# SL1_Xilinx_Spartan-IIE_PQ208_Rev1_02.net
KiCad netlist of a schematic drawn in Altium Designer
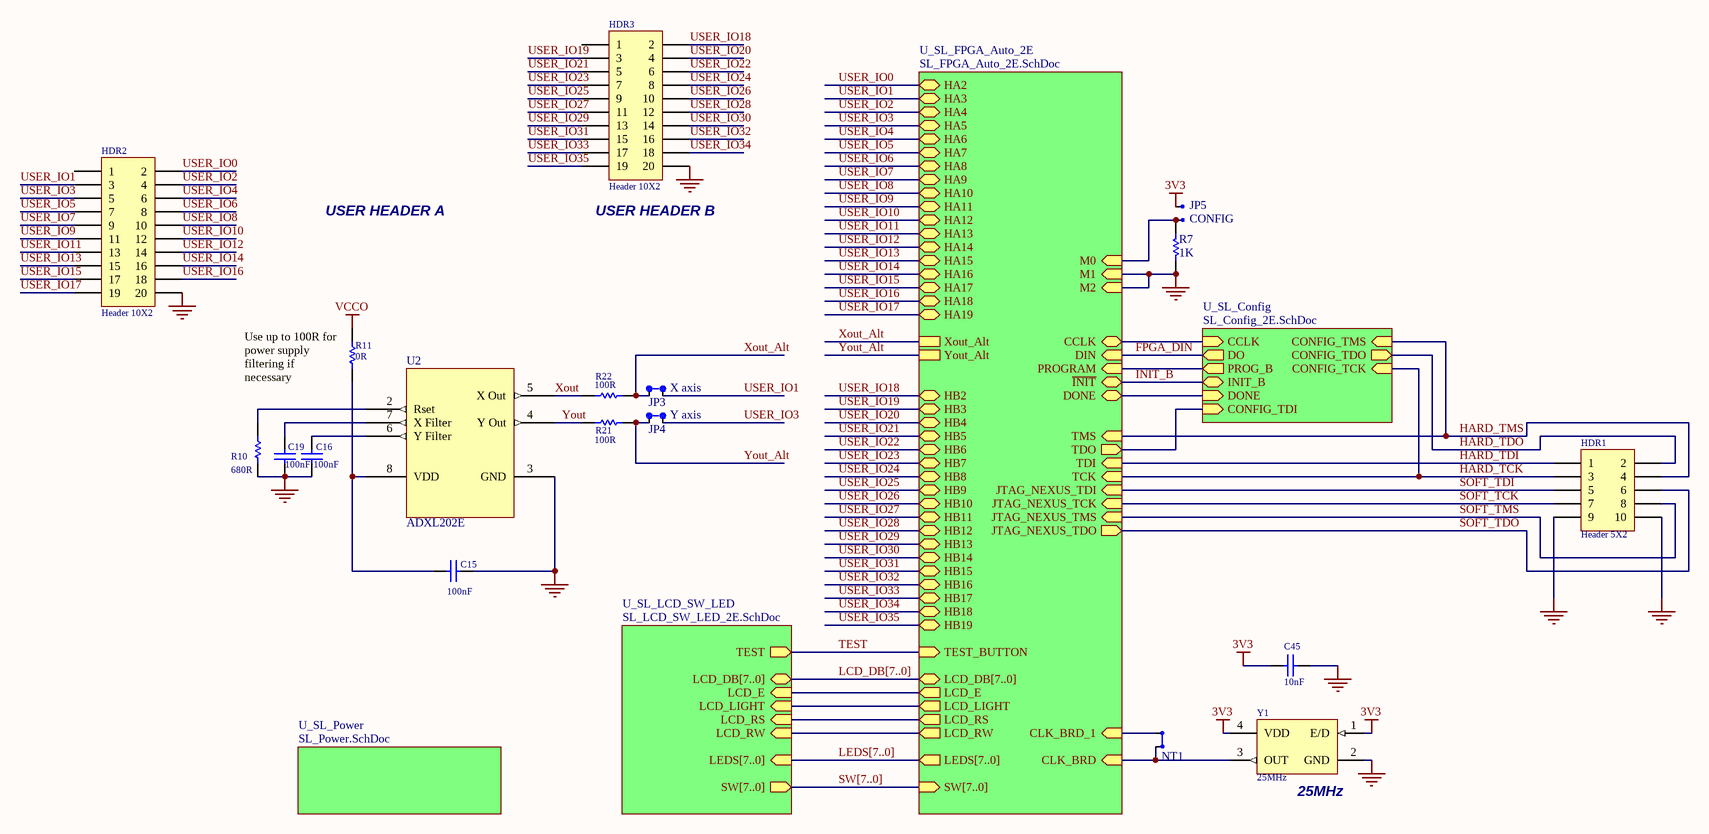
[diagram p0: SL1 Xilinx Spartan-IIE PQ208 Rev1.02.SchDoc]

(export (version "E")
  (design (tool "Eeschema 10.0.6"))
  (components
    (comp (ref "C15")
      (value "100nF")
      (footprint "CC1608-0603")
      (description "Capacitor")
      (libsource (lib "SpiritLevel_2E") (part "CAP"))
    )
    (comp (ref "C16")
      (value "100nF")
      (footprint "CC1608-0603")
      (description "Capacitor")
      (libsource (lib "SpiritLevel_2E") (part "CAP"))
    )
    (comp (ref "C19")
      (value "100nF")
      (footprint "CC1608-0603")
      (description "Capacitor")
      (libsource (lib "SpiritLevel_2E") (part "CAP"))
    )
    (comp (ref "C45")
      (value "10nF")
      (footprint "CC1608-0603")
      (description "Capacitor")
      (libsource (lib "SpiritLevel_2E") (part "CAP"))
    )
    (comp (ref "HDR1")
      (value "Header 5X2")
      (footprint "Spirit_Level_Project:HDR2X5_LP")
      (description "Header, 5-Pin, Dual row")
      (libsource (lib "SpiritLevel_2E") (part "Header 5X2"))
    )
    (comp (ref "HDR2")
      (value "Header 10X2")
      (footprint "Spirit_Level_Project:HDR2X10")
      (description "Header, 10-Pin, Dual row")
      (libsource (lib "SpiritLevel_2E") (part "Header 10X2"))
    )
    (comp (ref "HDR3")
      (value "Header 10X2")
      (footprint "Spirit_Level_Project:HDR2X10")
      (description "Header, 10-Pin, Dual row")
      (libsource (lib "SpiritLevel_2E") (part "Header 10X2"))
    )
    (comp (ref "JP3")
      (value "X axis")
      (footprint "Spirit_Level_Project:HDR1X2")
      (description "Jumper, 2-Pin")
      (libsource (lib "SpiritLevel_2E") (part "Jumper, 2-Pin"))
    )
    (comp (ref "JP4")
      (value "Y axis")
      (footprint "Spirit_Level_Project:HDR1X2")
      (description "Jumper, 2-Pin")
      (libsource (lib "SpiritLevel_2E") (part "Jumper, 2-Pin"))
    )
    (comp (ref "JP5")
      (value "CONFIG")
      (footprint "Spirit_Level_Project:HDR1X2")
      (description "Jumper, 2-Pin")
      (libsource (lib "SpiritLevel_2E") (part "Jumper, 2-Pin"))
    )
    (comp (ref "JS2")
      (value "Short Linking")
      (description "Shorting Link, 2.54mm (0.1\") Pitch")
      (libsource (lib "SpiritLevel_2E") (part "Jumper Socket"))
    )
    (comp (ref "JS3")
      (value "Shorting Link")
      (description "Shorting Link, 2.54mm (0.1\") Pitch")
      (libsource (lib "SpiritLevel_2E") (part "Jumper Socket"))
    )
    (comp (ref "NT1")
      (value "GND")
      (footprint "Spirit_Level_Project:NT")
      (description "Jumper, 2-Pin")
      (libsource (lib "SpiritLevel_2E") (part "Jumper, 2-Pin_1"))
    )
    (comp (ref "R7")
      (value "1K")
      (footprint "Spirit_Level_Project:CR2012-0805")
      (description "Resistor")
      (libsource (lib "SpiritLevel_2E") (part "RES"))
    )
    (comp (ref "R10")
      (value "680R")
      (footprint "Spirit_Level_Project:CR2012-0805")
      (description "Resistor")
      (libsource (lib "SpiritLevel_2E") (part "Res1"))
    )
    (comp (ref "R11")
      (value "0R")
      (footprint "Spirit_Level_Project:CR2012-0805")
      (description "Resistor")
      (libsource (lib "SpiritLevel_2E") (part "RES"))
    )
    (comp (ref "R21")
      (value "100R")
      (footprint "Spirit_Level_Project:CR2012-0805")
      (description "Resistor")
      (libsource (lib "SpiritLevel_2E") (part "Res1"))
    )
    (comp (ref "R22")
      (value "100R")
      (footprint "Spirit_Level_Project:CR2012-0805")
      (description "Resistor")
      (libsource (lib "SpiritLevel_2E") (part "Res1"))
    )
    (comp (ref "U2")
      (value "ADXL202E")
      (footprint "Spirit_Level_Project:E-8")
      (description "Accelerometer with Digital Output")
      (libsource (lib "SpiritLevel_2E") (part "ADXL202E"))
    )
    (comp (ref "Y1")
      (value "25MHz")
      (footprint "Spirit_Level_Project:QSMO_4200")
      (description "Surface Mount Crystal Oscillator")
      (libsource (lib "SpiritLevel_2E") (part "QSMO_4200"))
    )
  )
  (nets
    (net (code "26") (name "/CLK_BRD") (class "Default")
      (node (ref "NT1") (pin "2") (pinfunction "2_2") (pintype "passive"))
      (node (ref "Y1") (pin "3") (pinfunction "OUT_3") (pintype "output"))
    )
    (net (code "27") (name "/CLK_BRD_1") (class "Default")
      (node (ref "NT1") (pin "1") (pinfunction "1_1") (pintype "passive"))
    )
    (net (code "30") (name "/HARD_TCK") (class "Default")
      (node (ref "HDR1") (pin "3") (pinfunction "3_3") (pintype "passive"))
    )
    (net (code "31") (name "/HARD_TDI") (class "Default")
      (node (ref "HDR1") (pin "1") (pinfunction "1_1") (pintype "passive"))
    )
    (net (code "32") (name "/HARD_TDO") (class "Default")
      (node (ref "HDR1") (pin "2") (pinfunction "2_2") (pintype "passive"))
    )
    (net (code "33") (name "/HARD_TMS") (class "Default")
      (node (ref "HDR1") (pin "4") (pinfunction "4_4") (pintype "passive"))
    )
    (net (code "41") (name "/M0") (class "Default")
      (node (ref "JP5") (pin "1") (pinfunction "1_1") (pintype "passive"))
      (node (ref "R7") (pin "2") (pinfunction "2_2") (pintype "passive"))
    )
    (net (code "43") (name "/SOFT_TCK") (class "Default")
      (node (ref "HDR1") (pin "7") (pinfunction "7_7") (pintype "passive"))
    )
    (net (code "44") (name "/SOFT_TDI") (class "Default")
      (node (ref "HDR1") (pin "5") (pinfunction "5_5") (pintype "passive"))
    )
    (net (code "45") (name "/SOFT_TDO") (class "Default")
      (node (ref "HDR1") (pin "6") (pinfunction "6_6") (pintype "passive"))
    )
    (net (code "46") (name "/SOFT_TMS") (class "Default")
      (node (ref "HDR1") (pin "8") (pinfunction "8_8") (pintype "passive"))
    )
    (net (code "50") (name "/USER_IO0") (class "Default")
      (node (ref "HDR2") (pin "2") (pinfunction "2_2") (pintype "passive"))
    )
    (net (code "51") (name "/USER_IO1") (class "Default")
      (node (ref "HDR2") (pin "3") (pinfunction "3_3") (pintype "passive"))
      (node (ref "JP3") (pin "2") (pinfunction "2_2") (pintype "passive"))
    )
    (net (code "52") (name "/USER_IO2") (class "Default")
      (node (ref "HDR2") (pin "4") (pinfunction "4_4") (pintype "passive"))
    )
    (net (code "53") (name "/USER_IO3") (class "Default")
      (node (ref "HDR2") (pin "5") (pinfunction "5_5") (pintype "passive"))
      (node (ref "JP4") (pin "2") (pinfunction "2_2") (pintype "passive"))
    )
    (net (code "54") (name "/USER_IO4") (class "Default")
      (node (ref "HDR2") (pin "6") (pinfunction "6_6") (pintype "passive"))
    )
    (net (code "55") (name "/USER_IO5") (class "Default")
      (node (ref "HDR2") (pin "7") (pinfunction "7_7") (pintype "passive"))
    )
    (net (code "56") (name "/USER_IO6") (class "Default")
      (node (ref "HDR2") (pin "8") (pinfunction "8_8") (pintype "passive"))
    )
    (net (code "57") (name "/USER_IO7") (class "Default")
      (node (ref "HDR2") (pin "9") (pinfunction "9_9") (pintype "passive"))
    )
    (net (code "58") (name "/USER_IO8") (class "Default")
      (node (ref "HDR2") (pin "10") (pinfunction "10_10") (pintype "passive"))
    )
    (net (code "59") (name "/USER_IO9") (class "Default")
      (node (ref "HDR2") (pin "11") (pinfunction "11_11") (pintype "passive"))
    )
    (net (code "60") (name "/USER_IO10") (class "Default")
      (node (ref "HDR2") (pin "12") (pinfunction "12_12") (pintype "passive"))
    )
    (net (code "61") (name "/USER_IO11") (class "Default")
      (node (ref "HDR2") (pin "13") (pinfunction "13_13") (pintype "passive"))
    )
    (net (code "62") (name "/USER_IO12") (class "Default")
      (node (ref "HDR2") (pin "14") (pinfunction "14_14") (pintype "passive"))
    )
    (net (code "63") (name "/USER_IO13") (class "Default")
      (node (ref "HDR2") (pin "15") (pinfunction "15_15") (pintype "passive"))
    )
    (net (code "64") (name "/USER_IO14") (class "Default")
      (node (ref "HDR2") (pin "16") (pinfunction "16_16") (pintype "passive"))
    )
    (net (code "65") (name "/USER_IO15") (class "Default")
      (node (ref "HDR2") (pin "17") (pinfunction "17_17") (pintype "passive"))
    )
    (net (code "66") (name "/USER_IO16") (class "Default")
      (node (ref "HDR2") (pin "18") (pinfunction "18_18") (pintype "passive"))
    )
    (net (code "67") (name "/USER_IO17") (class "Default")
      (node (ref "HDR2") (pin "19") (pinfunction "19_19") (pintype "passive"))
    )
    (net (code "68") (name "/USER_IO18") (class "Default")
      (node (ref "HDR3") (pin "2") (pinfunction "2_2") (pintype "passive"))
    )
    (net (code "69") (name "/USER_IO19") (class "Default")
      (node (ref "HDR3") (pin "3") (pinfunction "3_3") (pintype "passive"))
    )
    (net (code "70") (name "/USER_IO20") (class "Default")
      (node (ref "HDR3") (pin "4") (pinfunction "4_4") (pintype "passive"))
    )
    (net (code "71") (name "/USER_IO21") (class "Default")
      (node (ref "HDR3") (pin "5") (pinfunction "5_5") (pintype "passive"))
    )
    (net (code "72") (name "/USER_IO22") (class "Default")
      (node (ref "HDR3") (pin "6") (pinfunction "6_6") (pintype "passive"))
    )
    (net (code "73") (name "/USER_IO23") (class "Default")
      (node (ref "HDR3") (pin "7") (pinfunction "7_7") (pintype "passive"))
    )
    (net (code "74") (name "/USER_IO24") (class "Default")
      (node (ref "HDR3") (pin "8") (pinfunction "8_8") (pintype "passive"))
    )
    (net (code "75") (name "/USER_IO25") (class "Default")
      (node (ref "HDR3") (pin "9") (pinfunction "9_9") (pintype "passive"))
    )
    (net (code "76") (name "/USER_IO26") (class "Default")
      (node (ref "HDR3") (pin "10") (pinfunction "10_10") (pintype "passive"))
    )
    (net (code "77") (name "/USER_IO27") (class "Default")
      (node (ref "HDR3") (pin "11") (pinfunction "11_11") (pintype "passive"))
    )
    (net (code "78") (name "/USER_IO28") (class "Default")
      (node (ref "HDR3") (pin "12") (pinfunction "12_12") (pintype "passive"))
    )
    (net (code "79") (name "/USER_IO29") (class "Default")
      (node (ref "HDR3") (pin "13") (pinfunction "13_13") (pintype "passive"))
    )
    (net (code "80") (name "/USER_IO30") (class "Default")
      (node (ref "HDR3") (pin "14") (pinfunction "14_14") (pintype "passive"))
    )
    (net (code "81") (name "/USER_IO31") (class "Default")
      (node (ref "HDR3") (pin "15") (pinfunction "15_15") (pintype "passive"))
    )
    (net (code "82") (name "/USER_IO32") (class "Default")
      (node (ref "HDR3") (pin "16") (pinfunction "16_16") (pintype "passive"))
    )
    (net (code "83") (name "/USER_IO33") (class "Default")
      (node (ref "HDR3") (pin "17") (pinfunction "17_17") (pintype "passive"))
    )
    (net (code "84") (name "/USER_IO34") (class "Default")
      (node (ref "HDR3") (pin "18") (pinfunction "18_18") (pintype "passive"))
    )
    (net (code "85") (name "/USER_IO35") (class "Default")
      (node (ref "HDR3") (pin "19") (pinfunction "19_19") (pintype "passive"))
    )
    (net (code "86") (name "/Xout") (class "Default")
      (node (ref "R22") (pin "2") (pinfunction "2_2") (pintype "passive"))
      (node (ref "U2") (pin "5") (pinfunction "X_Out_5") (pintype "output"))
    )
    (net (code "87") (name "/Xout_Alt") (class "Default")
      (node (ref "JP3") (pin "1") (pinfunction "1_1") (pintype "passive"))
      (node (ref "R22") (pin "1") (pinfunction "1_1") (pintype "passive"))
    )
    (net (code "88") (name "/Yout") (class "Default")
      (node (ref "R21") (pin "2") (pinfunction "2_2") (pintype "passive"))
      (node (ref "U2") (pin "4") (pinfunction "Y_Out_4") (pintype "output"))
    )
    (net (code "89") (name "/Yout_Alt") (class "Default")
      (node (ref "JP4") (pin "1") (pinfunction "1_1") (pintype "passive"))
      (node (ref "R21") (pin "1") (pinfunction "1_1") (pintype "passive"))
    )
    (net (code "90") (name "3V3") (class "Default")
      (node (ref "C45") (pin "1") (pinfunction "1_1") (pintype "passive"))
      (node (ref "JP5") (pin "2") (pinfunction "2_2") (pintype "passive"))
      (node (ref "Y1") (pin "1") (pinfunction "E/D_1") (pintype "input"))
      (node (ref "Y1") (pin "4") (pinfunction "VDD_4") (pintype "power_in"))
    )
    (net (code "91") (name "GND") (class "Default")
      (node (ref "C15") (pin "2") (pinfunction "2_2") (pintype "passive"))
      (node (ref "C16") (pin "2") (pinfunction "2_2") (pintype "passive"))
      (node (ref "C19") (pin "2") (pinfunction "2_2") (pintype "passive"))
      (node (ref "C45") (pin "2") (pinfunction "2_2") (pintype "passive"))
      (node (ref "HDR1") (pin "10") (pinfunction "10_10") (pintype "passive"))
      (node (ref "HDR1") (pin "9") (pinfunction "9_9") (pintype "passive"))
      (node (ref "HDR2") (pin "20") (pinfunction "20_20") (pintype "passive"))
      (node (ref "HDR3") (pin "20") (pinfunction "20_20") (pintype "passive"))
      (node (ref "R10") (pin "1") (pinfunction "1_1") (pintype "passive"))
      (node (ref "R7") (pin "1") (pinfunction "1_1") (pintype "passive"))
      (node (ref "U2") (pin "3") (pinfunction "GND_3") (pintype "power_in"))
      (node (ref "Y1") (pin "2") (pinfunction "GND_2") (pintype "power_in"))
    )
    (net (code "92") (name "Net-(U2-Rset)") (class "Default")
      (node (ref "R10") (pin "2") (pinfunction "2_2") (pintype "passive"))
      (node (ref "U2") (pin "2") (pinfunction "Rset_2") (pintype "output"))
    )
    (net (code "93") (name "Net-(U2-VDD)") (class "Default")
      (node (ref "C15") (pin "1") (pinfunction "1_1") (pintype "passive"))
      (node (ref "R11") (pin "2") (pinfunction "2_2") (pintype "passive"))
      (node (ref "U2") (pin "8") (pinfunction "VDD_8") (pintype "power_in"))
    )
    (net (code "94") (name "Net-(U2-X_Filter)") (class "Default")
      (node (ref "C19") (pin "1") (pinfunction "1_1") (pintype "passive"))
      (node (ref "U2") (pin "7") (pinfunction "X_Filter_7") (pintype "output"))
    )
    (net (code "95") (name "Net-(U2-Y_Filter)") (class "Default")
      (node (ref "C16") (pin "1") (pinfunction "1_1") (pintype "passive"))
      (node (ref "U2") (pin "6") (pinfunction "Y_Filter_6") (pintype "output"))
    )
    (net (code "96") (name "VCCO") (class "Default")
      (node (ref "R11") (pin "1") (pinfunction "1_1") (pintype "passive"))
    )
    (net (code "97") (name "unconnected-(HDR2-Pad1)") (class "Default")
      (node (ref "HDR2") (pin "1") (pinfunction "1_1") (pintype "passive"))
    )
    (net (code "98") (name "unconnected-(HDR3-Pad1)") (class "Default")
      (node (ref "HDR3") (pin "1") (pinfunction "1_1") (pintype "passive"))
    )
    (net (code "99") (name "unconnected-(U2-Self_Test-Pad1)") (class "Default")
      (node (ref "U2") (pin "1") (pinfunction "Self_Test_1") (pintype "input"))
    )
  )
)
